# Connector_and_Protection.net
KiCad netlist of a schematic drawn in Altium Designer
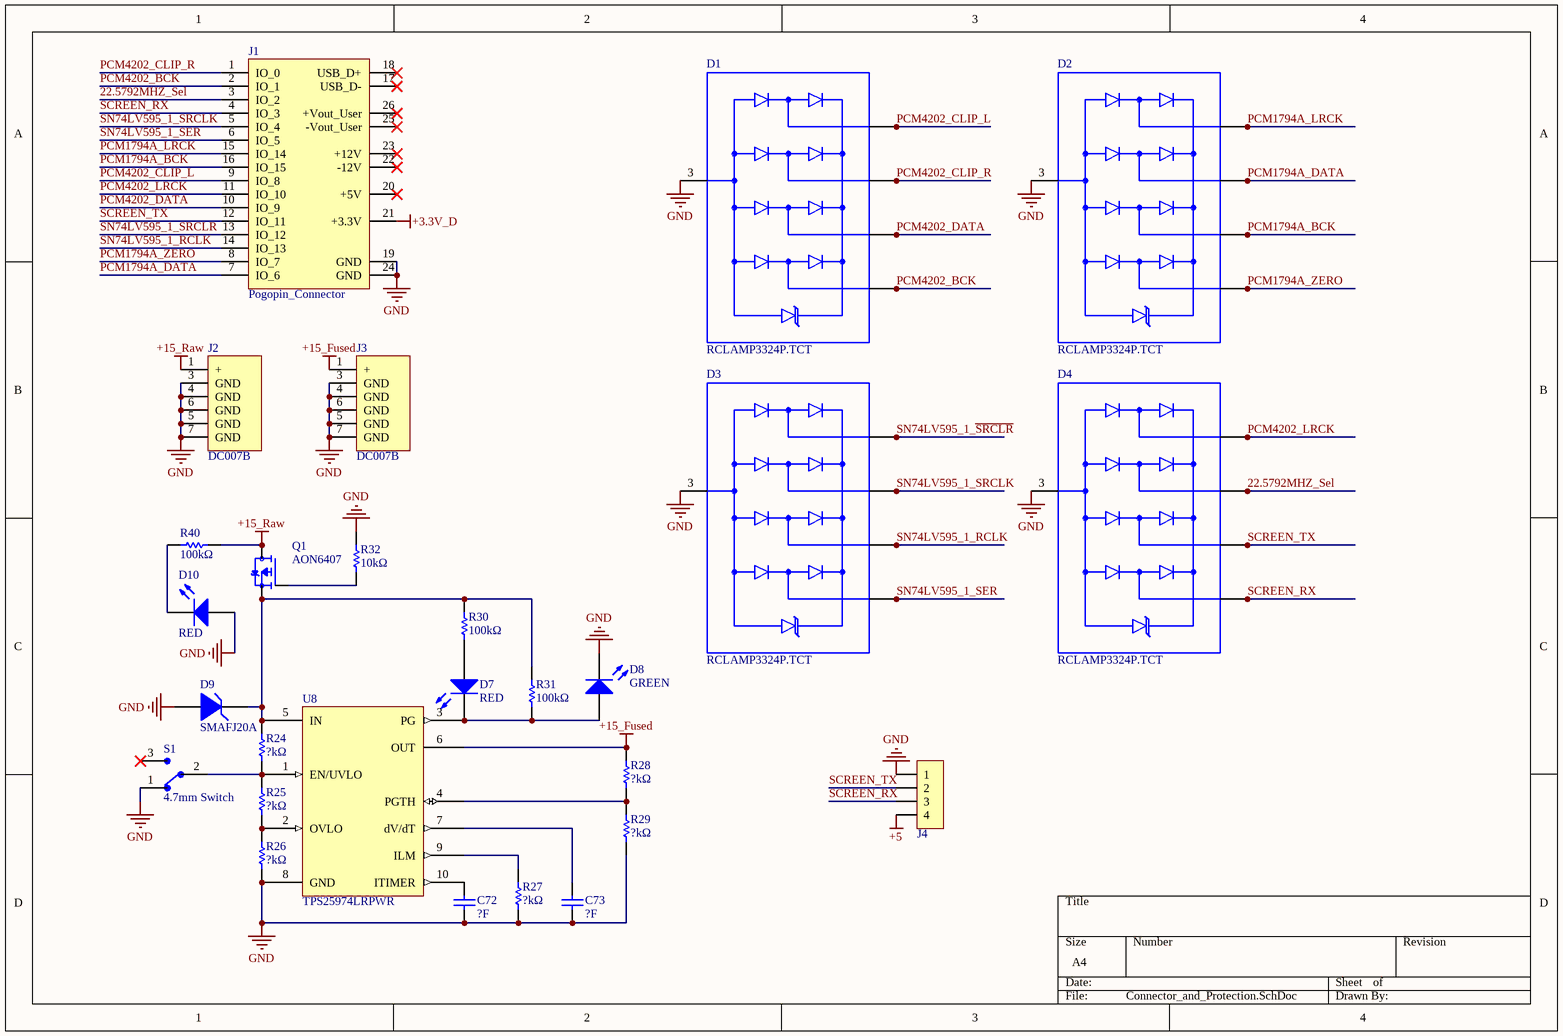
[diagram p0: Connector_and_Protection.SchDoc]

(export (version "E")
  (design (tool "Eeschema 10.0.6"))
  (components
    (comp (ref "C72")
      (value "?F")
      (footprint "C 0402_L")
      (description "Capacitor")
      (fields (field (name "PUBLISHER") "Altium Limited"))
      (libsource (lib "Miscellaneous Devices") (part "Cap"))
    )
    (comp (ref "C73")
      (value "?F")
      (footprint "C 0402_L")
      (description "Capacitor")
      (fields (field (name "PUBLISHER") "Altium Limited"))
      (libsource (lib "Miscellaneous Devices") (part "Cap"))
    )
    (comp (ref "D1")
      (value "RCLAMP3324P.TCT")
      (footprint "DIO_RCLAMP3324P.TCT")
      (description "4.5V Clamp 4.5A _8/20Âµs_ Ipp Tvs Diode Surface Mount SGP2510P8")
      (fields (field (name "MF") "Semtech Corporation"))
      (libsource (lib "RCLAMP3324PTCT") (part "RCLAMP3324P.TCT"))
    )
    (comp (ref "D2")
      (value "RCLAMP3324P.TCT")
      (footprint "DIO_RCLAMP3324P.TCT")
      (description "4.5V Clamp 4.5A _8/20Âµs_ Ipp Tvs Diode Surface Mount SGP2510P8")
      (fields (field (name "MF") "Semtech Corporation"))
      (libsource (lib "RCLAMP3324PTCT") (part "RCLAMP3324P.TCT"))
    )
    (comp (ref "D3")
      (value "RCLAMP3324P.TCT")
      (footprint "DIO_RCLAMP3324P.TCT")
      (description "4.5V Clamp 4.5A _8/20Âµs_ Ipp Tvs Diode Surface Mount SGP2510P8")
      (fields (field (name "MF") "Semtech Corporation"))
      (libsource (lib "RCLAMP3324PTCT") (part "RCLAMP3324P.TCT"))
    )
    (comp (ref "D4")
      (value "RCLAMP3324P.TCT")
      (footprint "DIO_RCLAMP3324P.TCT")
      (description "4.5V Clamp 4.5A _8/20Âµs_ Ipp Tvs Diode Surface Mount SGP2510P8")
      (fields (field (name "MF") "Semtech Corporation"))
      (libsource (lib "RCLAMP3324PTCT") (part "RCLAMP3324P.TCT"))
    )
    (comp (ref "D7")
      (value "RED")
      (footprint "LED 0603R")
      (description "Typical INFRARED GaAs LED")
      (fields (field (name "PUBLISHER") "Altium Limited"))
      (libsource (lib "Miscellaneous Devices") (part "LED0"))
    )
    (comp (ref "D8")
      (value "GREEN")
      (footprint "LED 0603B")
      (description "Typical INFRARED GaAs LED")
      (fields (field (name "PUBLISHER") "Altium Limited"))
      (libsource (lib "Miscellaneous Devices") (part "LED0"))
    )
    (comp (ref "D9")
      (value "SMAFJ20A")
      (footprint "VISH-DO-214AC-2_L")
      (libsource (lib "SMAFJ20A") (part "CMP-0548-00226-2"))
    )
    (comp (ref "D10")
      (value "RED")
      (footprint "LED 0603R")
      (description "Typical INFRARED GaAs LED")
      (fields (field (name "PUBLISHER") "Altium Limited"))
      (libsource (lib "Miscellaneous Devices") (part "LED0"))
    )
    (comp (ref "J1")
      (value "Pogopin_Connector")
      (footprint "26P_Pogopin")
      (description "Pogopin connector suits Raindrop-S")
      (libsource (lib "Pogopin_Connector") (part "Pogopin_Connector"))
    )
    (comp (ref "J2")
      (value "DC007B")
      (footprint "CONN2_ADC-096-2-T/R_ADM")
      (description "5521")
      (fields
        (field (name "MANUFACTURER_PART_NUMBER") "ADC-096-2-T/R")
        (field (name "COPYRIGHT") "Copyright (C) 2022 Ultra Librarian. All rights reserved.")
      )
      (libsource (lib "DC007B") (part "DC007B"))
    )
    (comp (ref "J3")
      (value "DC007B")
      (footprint "CONN2_ADC-096-2-T/R_ADM")
      (description "5521")
      (fields
        (field (name "MANUFACTURER_PART_NUMBER") "ADC-096-2-T/R")
        (field (name "COPYRIGHT") "Copyright (C) 2022 Ultra Librarian. All rights reserved.")
      )
      (libsource (lib "DC007B") (part "DC007B"))
    )
    (comp (ref "J4")
      (value "HDR-1X4")
      (footprint "XH2.54-WI-4P")
      (libsource (lib "XH2.54_4P") (part "Header 4"))
    )
    (comp (ref "Q1")
      (value "AON6407")
      (footprint "TRANS_AON6407")
      (description "P-Channel 30V 32A (Ta), 85A (Tc) 7.3W (Ta), 83W (Tc) Surface Mount 8-DFN (5x6)")
      (fields (field (name "DIGI-KEY_PART_NUMBER") "785-1421-1-ND") (field (name "MF") "Alpha &"))
      (libsource (lib "AON6407") (part "AON6407"))
    )
    (comp (ref "R24")
      (value "?kΩ")
      (footprint "R 0402_L")
      (description "Resistor")
      (fields (field (name "PUBLISHER") "Altium Limited"))
      (libsource (lib "Miscellaneous Devices") (part "Res1"))
    )
    (comp (ref "R25")
      (value "?kΩ")
      (footprint "R 0402_L")
      (description "Resistor")
      (fields (field (name "PUBLISHER") "Altium Limited"))
      (libsource (lib "Miscellaneous Devices") (part "Res1"))
    )
    (comp (ref "R26")
      (value "?kΩ")
      (footprint "R 0402_L")
      (description "Resistor")
      (fields (field (name "PUBLISHER") "Altium Limited"))
      (libsource (lib "Miscellaneous Devices") (part "Res1"))
    )
    (comp (ref "R27")
      (value "?kΩ")
      (footprint "R 0402_L")
      (description "Resistor")
      (fields (field (name "PUBLISHER") "Altium Limited"))
      (libsource (lib "Miscellaneous Devices") (part "Res1"))
    )
    (comp (ref "R28")
      (value "?kΩ")
      (footprint "R 0402_L")
      (description "Resistor")
      (fields (field (name "PUBLISHER") "Altium Limited"))
      (libsource (lib "Miscellaneous Devices") (part "Res1"))
    )
    (comp (ref "R29")
      (value "?kΩ")
      (footprint "R 0402_L")
      (description "Resistor")
      (fields (field (name "PUBLISHER") "Altium Limited"))
      (libsource (lib "Miscellaneous Devices") (part "Res1"))
    )
    (comp (ref "R30")
      (value "100kΩ")
      (footprint "R 0402_L")
      (description "Resistor")
      (fields (field (name "PUBLISHER") "Altium Limited"))
      (libsource (lib "Miscellaneous Devices") (part "Res1"))
    )
    (comp (ref "R31")
      (value "100kΩ")
      (footprint "R 0402_L")
      (description "Resistor")
      (fields (field (name "PUBLISHER") "Altium Limited"))
      (libsource (lib "Miscellaneous Devices") (part "Res1"))
    )
    (comp (ref "R32")
      (value "10kΩ")
      (footprint "R 0402_L")
      (description "Resistor")
      (fields (field (name "PUBLISHER") "Altium Limited"))
      (libsource (lib "Miscellaneous Devices") (part "Res1"))
    )
    (comp (ref "R40")
      (value "100kΩ")
      (footprint "R 0402_L")
      (description "Resistor")
      (fields (field (name "PUBLISHER") "Altium Limited"))
      (libsource (lib "Miscellaneous Devices") (part "Res1"))
    )
    (comp (ref "S1")
      (value "4.7mm Switch")
      (footprint "SW_1101M2S3CQE2")
      (description "Slide Switch SPDT Through Hole")
      (fields (field (name "MP") "1101M2S3CQE2") (field (name "DIGI-KEY_PART_NUMBER") "CKN5001-ND"))
      (libsource (lib "Power_Switch") (part "4.7mm Switch"))
    )
    (comp (ref "U8")
      (value "TPS25974LRPWR")
      (footprint "VQFN8_PWR_TEX")
      (description "No Description Available")
      (libsource (lib "TPS25974L") (part "TPS25974LRPWR"))
    )
  )
  (nets
    (net (code "1") (name "+3.3V_D") (class "Default")
      (node (ref "J1") (pin "21") (pinfunction "+3.3V_21") (pintype "passive"))
    )
    (net (code "2") (name "+5") (class "Default")
      (node (ref "J4") (pin "4") (pinfunction "4_4") (pintype "passive"))
    )
    (net (code "3") (name "+15_Fused") (class "Default")
      (node (ref "J3") (pin "1") (pinfunction "+_1") (pintype "passive"))
      (node (ref "R28") (pin "2") (pinfunction "2_2") (pintype "passive"))
      (node (ref "U8") (pin "6") (pinfunction "OUT_6") (pintype "power_in"))
    )
    (net (code "4") (name "+15_Raw") (class "Default")
      (node (ref "J2") (pin "1") (pinfunction "+_1") (pintype "passive"))
      (node (ref "Q1") (pin "5_8") (pinfunction "D_5_8") (pintype "passive"))
      (node (ref "R40") (pin "1") (pinfunction "1_1") (pintype "passive"))
    )
    (net (code "5") (name "/22.5792MHZ_Sel") (class "Default")
      (node (ref "D4") (pin "2") (pinfunction "2_2") (pintype "passive"))
      (node (ref "J1") (pin "3") (pinfunction "IO_2_3") (pintype "passive"))
    )
    (net (code "6") (name "/PCM1794A_BCK") (class "Default")
      (node (ref "D2") (pin "4") (pinfunction "4_4") (pintype "passive"))
      (node (ref "J1") (pin "16") (pinfunction "IO_15_16") (pintype "passive"))
    )
    (net (code "7") (name "/PCM1794A_DATA") (class "Default")
      (node (ref "D2") (pin "2") (pinfunction "2_2") (pintype "passive"))
      (node (ref "J1") (pin "7") (pinfunction "IO_6_7") (pintype "passive"))
    )
    (net (code "8") (name "/PCM1794A_LRCK") (class "Default")
      (node (ref "D2") (pin "1") (pinfunction "1_1") (pintype "passive"))
      (node (ref "J1") (pin "15") (pinfunction "IO_14_15") (pintype "passive"))
    )
    (net (code "9") (name "/PCM1794A_ZERO") (class "Default")
      (node (ref "D2") (pin "5") (pinfunction "5_5") (pintype "passive"))
      (node (ref "J1") (pin "8") (pinfunction "IO_7_8") (pintype "passive"))
    )
    (net (code "10") (name "/PCM4202_BCK") (class "Default")
      (node (ref "D1") (pin "5") (pinfunction "5_5") (pintype "passive"))
      (node (ref "J1") (pin "2") (pinfunction "IO_1_2") (pintype "passive"))
    )
    (net (code "11") (name "/PCM4202_CLIP_L") (class "Default")
      (node (ref "D1") (pin "1") (pinfunction "1_1") (pintype "passive"))
      (node (ref "J1") (pin "9") (pinfunction "IO_8_9") (pintype "passive"))
    )
    (net (code "12") (name "/PCM4202_CLIP_R") (class "Default")
      (node (ref "D1") (pin "2") (pinfunction "2_2") (pintype "passive"))
      (node (ref "J1") (pin "1") (pinfunction "IO_0_1") (pintype "passive"))
    )
    (net (code "13") (name "/PCM4202_DATA") (class "Default")
      (node (ref "D1") (pin "4") (pinfunction "4_4") (pintype "passive"))
      (node (ref "J1") (pin "10") (pinfunction "IO_9_10") (pintype "passive"))
    )
    (net (code "14") (name "/PCM4202_LRCK") (class "Default")
      (node (ref "D4") (pin "1") (pinfunction "1_1") (pintype "passive"))
      (node (ref "J1") (pin "11") (pinfunction "IO_10_11") (pintype "passive"))
    )
    (net (code "15") (name "/SCREEN_RX") (class "Default")
      (node (ref "D4") (pin "5") (pinfunction "5_5") (pintype "passive"))
      (node (ref "J1") (pin "4") (pinfunction "IO_3_4") (pintype "passive"))
      (node (ref "J4") (pin "3") (pinfunction "3_3") (pintype "passive"))
    )
    (net (code "16") (name "/SCREEN_TX") (class "Default")
      (node (ref "D4") (pin "4") (pinfunction "4_4") (pintype "passive"))
      (node (ref "J1") (pin "12") (pinfunction "IO_11_12") (pintype "passive"))
      (node (ref "J4") (pin "2") (pinfunction "2_2") (pintype "passive"))
    )
    (net (code "17") (name "/SN74LV595_1_RCLK") (class "Default")
      (node (ref "D3") (pin "4") (pinfunction "4_4") (pintype "passive"))
      (node (ref "J1") (pin "14") (pinfunction "IO_13_14") (pintype "passive"))
    )
    (net (code "18") (name "/SN74LV595_1_SER") (class "Default")
      (node (ref "D3") (pin "5") (pinfunction "5_5") (pintype "passive"))
      (node (ref "J1") (pin "6") (pinfunction "IO_5_6") (pintype "passive"))
    )
    (net (code "19") (name "/SN74LV595_1_SRCLK") (class "Default")
      (node (ref "D3") (pin "2") (pinfunction "2_2") (pintype "passive"))
      (node (ref "J1") (pin "5") (pinfunction "IO_4_5") (pintype "passive"))
    )
    (net (code "20") (name "/SN74LV595_1_~{SRCLR}") (class "Default")
      (node (ref "D3") (pin "1") (pinfunction "1_1") (pintype "passive"))
      (node (ref "J1") (pin "13") (pinfunction "IO_12_13") (pintype "passive"))
    )
    (net (code "21") (name "GND") (class "Default")
      (node (ref "C72") (pin "2") (pinfunction "2_2") (pintype "passive"))
      (node (ref "C73") (pin "2") (pinfunction "2_2") (pintype "passive"))
      (node (ref "D1") (pin "3") (pinfunction "GND_3") (pintype "passive"))
      (node (ref "D10") (pin "1") (pinfunction "A_1") (pintype "passive"))
      (node (ref "D2") (pin "3") (pinfunction "GND_3") (pintype "passive"))
      (node (ref "D3") (pin "3") (pinfunction "GND_3") (pintype "passive"))
      (node (ref "D4") (pin "3") (pinfunction "GND_3") (pintype "passive"))
      (node (ref "D8") (pin "2") (pinfunction "K_2") (pintype "passive"))
      (node (ref "D9") (pin "2") (pinfunction "A_2") (pintype "passive"))
      (node (ref "J1") (pin "19") (pinfunction "GND_19") (pintype "passive"))
      (node (ref "J1") (pin "24") (pinfunction "GND_24") (pintype "passive"))
      (node (ref "J2") (pin "3") (pinfunction "GND_3") (pintype "passive"))
      (node (ref "J2") (pin "4") (pinfunction "GND_4") (pintype "passive"))
      (node (ref "J2") (pin "5") (pinfunction "GND_5") (pintype "passive"))
      (node (ref "J2") (pin "6") (pinfunction "GND_6") (pintype "passive"))
      (node (ref "J2") (pin "7") (pinfunction "GND_7") (pintype "passive"))
      (node (ref "J3") (pin "3") (pinfunction "GND_3") (pintype "passive"))
      (node (ref "J3") (pin "4") (pinfunction "GND_4") (pintype "passive"))
      (node (ref "J3") (pin "5") (pinfunction "GND_5") (pintype "passive"))
      (node (ref "J3") (pin "6") (pinfunction "GND_6") (pintype "passive"))
      (node (ref "J3") (pin "7") (pinfunction "GND_7") (pintype "passive"))
      (node (ref "J4") (pin "1") (pinfunction "1_1") (pintype "passive"))
      (node (ref "R26") (pin "1") (pinfunction "1_1") (pintype "passive"))
      (node (ref "R27") (pin "1") (pinfunction "1_1") (pintype "passive"))
      (node (ref "R29") (pin "1") (pinfunction "1_1") (pintype "passive"))
      (node (ref "R32") (pin "1") (pinfunction "1_1") (pintype "passive"))
      (node (ref "S1") (pin "1") (pinfunction "1_1") (pintype "passive"))
      (node (ref "U8") (pin "8") (pinfunction "GND_8") (pintype "power_in"))
    )
    (net (code "22") (name "Net-(D7-A)") (class "Default")
      (node (ref "D7") (pin "1") (pinfunction "A_1") (pintype "passive"))
      (node (ref "R30") (pin "1") (pinfunction "1_1") (pintype "passive"))
    )
    (net (code "23") (name "Net-(D7-K)") (class "Default")
      (node (ref "D7") (pin "2") (pinfunction "K_2") (pintype "passive"))
      (node (ref "D8") (pin "1") (pinfunction "A_1") (pintype "passive"))
      (node (ref "R31") (pin "1") (pinfunction "1_1") (pintype "passive"))
      (node (ref "U8") (pin "3") (pinfunction "PG_3") (pintype "output"))
    )
    (net (code "24") (name "Net-(D9-K)") (class "Default")
      (node (ref "D9") (pin "1") (pinfunction "K_1") (pintype "passive"))
      (node (ref "Q1") (pin "1") (pinfunction "S_1") (pintype "passive"))
      (node (ref "Q1") (pin "2") (pinfunction "S_2") (pintype "passive"))
      (node (ref "Q1") (pin "3") (pinfunction "S_3") (pintype "passive"))
      (node (ref "R24") (pin "2") (pinfunction "2_2") (pintype "passive"))
      (node (ref "R30") (pin "2") (pinfunction "2_2") (pintype "passive"))
      (node (ref "R31") (pin "2") (pinfunction "2_2") (pintype "passive"))
      (node (ref "U8") (pin "5") (pinfunction "IN_5") (pintype "power_in"))
    )
    (net (code "25") (name "Net-(D10-K)") (class "Default")
      (node (ref "D10") (pin "2") (pinfunction "K_2") (pintype "passive"))
      (node (ref "R40") (pin "2") (pinfunction "2_2") (pintype "passive"))
    )
    (net (code "26") (name "Net-(Q1-G)") (class "Default")
      (node (ref "Q1") (pin "4") (pinfunction "G_4") (pintype "passive"))
      (node (ref "R32") (pin "2") (pinfunction "2_2") (pintype "passive"))
    )
    (net (code "27") (name "Net-(U8-EN{slash}UVLO)") (class "Default")
      (node (ref "R24") (pin "1") (pinfunction "1_1") (pintype "passive"))
      (node (ref "R25") (pin "2") (pinfunction "2_2") (pintype "passive"))
      (node (ref "S1") (pin "2") (pinfunction "2_2") (pintype "passive"))
      (node (ref "U8") (pin "1") (pinfunction "EN/UVLO_1") (pintype "input"))
    )
    (net (code "28") (name "Net-(U8-ILM)") (class "Default")
      (node (ref "R27") (pin "2") (pinfunction "2_2") (pintype "passive"))
      (node (ref "U8") (pin "9") (pinfunction "ILM_9") (pintype "output"))
    )
    (net (code "29") (name "Net-(U8-ITIMER)") (class "Default")
      (node (ref "C72") (pin "1") (pinfunction "1_1") (pintype "passive"))
      (node (ref "U8") (pin "10") (pinfunction "ITIMER_10") (pintype "output"))
    )
    (net (code "30") (name "Net-(U8-OVLO)") (class "Default")
      (node (ref "R25") (pin "1") (pinfunction "1_1") (pintype "passive"))
      (node (ref "R26") (pin "2") (pinfunction "2_2") (pintype "passive"))
      (node (ref "U8") (pin "2") (pinfunction "OVLO_2") (pintype "input"))
    )
    (net (code "31") (name "Net-(U8-PGTH)") (class "Default")
      (node (ref "R28") (pin "1") (pinfunction "1_1") (pintype "passive"))
      (node (ref "R29") (pin "2") (pinfunction "2_2") (pintype "passive"))
      (node (ref "U8") (pin "4") (pinfunction "PGTH_4") (pintype "bidirectional"))
    )
    (net (code "32") (name "Net-(U8-dV{slash}dT)") (class "Default")
      (node (ref "C73") (pin "1") (pinfunction "1_1") (pintype "passive"))
      (node (ref "U8") (pin "7") (pinfunction "dV/dT_7") (pintype "output"))
    )
    (net (code "33") (name "unconnected-(J1-+5V-Pad20)") (class "Default")
      (node (ref "J1") (pin "20") (pinfunction "+5V_20") (pintype "passive+no_connect"))
    )
    (net (code "34") (name "unconnected-(J1-+12V-Pad23)") (class "Default")
      (node (ref "J1") (pin "23") (pinfunction "+12V_23") (pintype "passive+no_connect"))
    )
    (net (code "35") (name "unconnected-(J1-+Vout_User-Pad26)") (class "Default")
      (node (ref "J1") (pin "26") (pinfunction "+Vout_User_26") (pintype "passive+no_connect"))
    )
    (net (code "36") (name "unconnected-(J1--12V-Pad22)") (class "Default")
      (node (ref "J1") (pin "22") (pinfunction "-12V_22") (pintype "passive+no_connect"))
    )
    (net (code "37") (name "unconnected-(J1--Vout_User-Pad25)") (class "Default")
      (node (ref "J1") (pin "25") (pinfunction "-Vout_User_25") (pintype "passive+no_connect"))
    )
    (net (code "38") (name "unconnected-(J1-USB_D+-Pad18)") (class "Default")
      (node (ref "J1") (pin "18") (pinfunction "USB_D+_18") (pintype "passive+no_connect"))
    )
    (net (code "39") (name "unconnected-(J1-USB_D--Pad17)") (class "Default")
      (node (ref "J1") (pin "17") (pinfunction "USB_D-_17") (pintype "passive+no_connect"))
    )
    (net (code "40") (name "unconnected-(S1-Pad3)") (class "Default")
      (node (ref "S1") (pin "3") (pinfunction "3_3") (pintype "passive+no_connect"))
    )
  )
)
